# StEth32_Power.net
KiCad netlist of a schematic drawn in Altium Designer
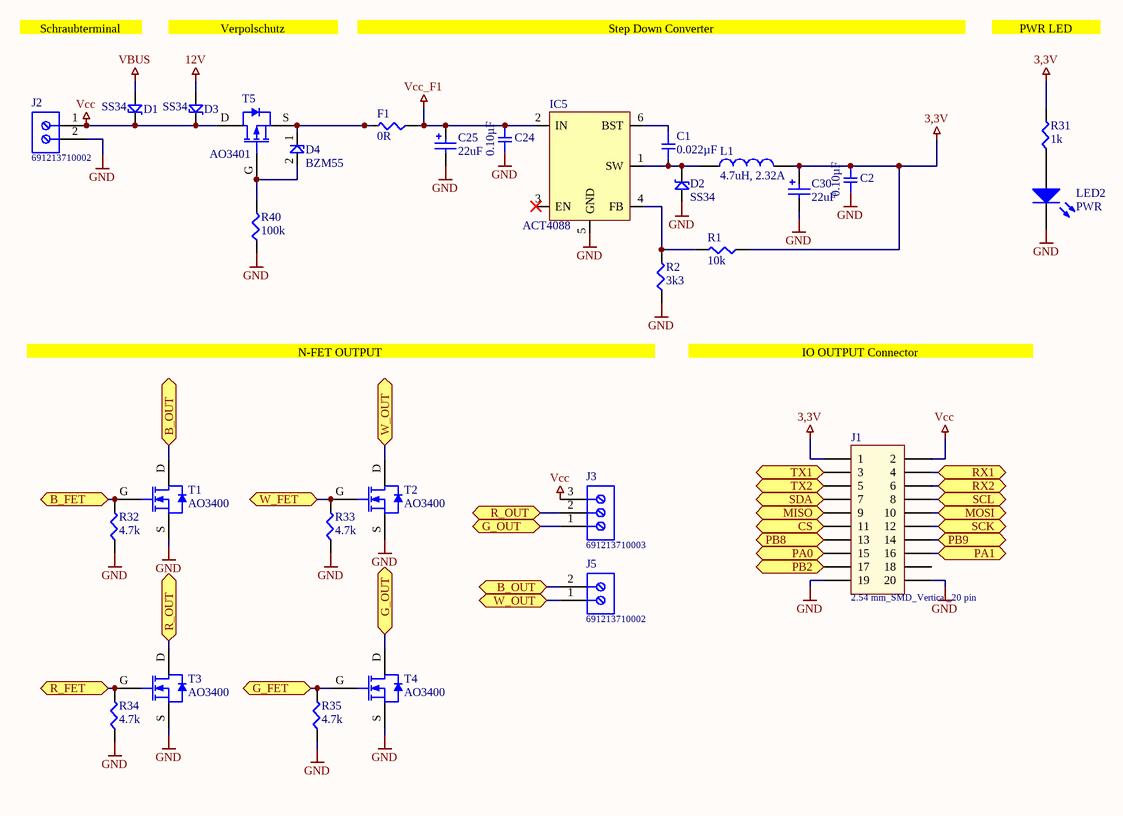
[diagram p0: StEth32_Power.SchDoc]

(export (version "E")
  (design (tool "Eeschema 10.0.6"))
  (components
    (comp (ref "C1")
      (value "0.022µF")
      (footprint "SMD-0603C")
      (description "CAP CER 0.022UF 50V X7R 0603")
      (fields
        (field (name "DIGI-KEY PART NUMBER") "490-5851-1-ND")
        (field (name "PART NUMBER") "GCJ188R71H223KA01D")
      )
      (libsource (lib "capacitor_murata_0603") (part "GCJ188R71H223KA01D"))
    )
    (comp (ref "C2")
      (value "0.10µF")
      (footprint "SMD-0603C")
      (description "CAP CER 0.1UF 16V X7R 0603")
      (fields
        (field (name "DIGI-KEY PART NUMBER") "490-8015-1-ND")
        (field (name "PART NUMBER") "GCM188R71C104KA37J")
      )
      (libsource (lib "capacitor_murata_0603") (part "GCM188R71C104KA37J"))
    )
    (comp (ref "C24")
      (value "0.10µF")
      (footprint "SMD-0603C")
      (description "CAP CER 0.1UF 16V X7R 0603")
      (fields
        (field (name "DIGI-KEY PART NUMBER") "490-8015-1-ND")
        (field (name "PART NUMBER") "GCM188R71C104KA37J")
      )
      (libsource (lib "capacitor_murata_0603") (part "GCM188R71C104KA37J"))
    )
    (comp (ref "C25")
      (value "22uF")
      (footprint "WCAP-ASLI_4x5.5")
      (description "WCAP-ASLI Aluminum Electrolytic Capacitors, size Ф4x5.5mm, 6.3V DC, 22uF")
      (fields (field (name "PART NUMBER") "865080140001") (field (name "PUBLISHER") "Wurth Elektronik"))
      (libsource (lib "ALTIUM-WCAP-ASLI-rev17a") (part "865080140001"))
    )
    (comp (ref "C30")
      (value "22uF")
      (footprint "WCAP-ASLI_4x5.5")
      (description "WCAP-ASLI Aluminum Electrolytic Capacitors, size Ф4x5.5mm, 6.3V DC, 22uF")
      (fields (field (name "PART NUMBER") "865080140001") (field (name "PUBLISHER") "Wurth Elektronik"))
      (libsource (lib "ALTIUM-WCAP-ASLI-rev17a") (part "865080140001"))
    )
    (comp (ref "D1")
      (value "SS34")
      (footprint "B240A")
      (description "Shottkydiode")
      (libsource (lib "MyLibs") (part "B240A"))
    )
    (comp (ref "D2")
      (value "SS34")
      (footprint "B240A")
      (description "Shottkydiode")
      (libsource (lib "MyLibs") (part "B240A"))
    )
    (comp (ref "D3")
      (value "SS34")
      (footprint "B240A")
      (description "Shottkydiode")
      (libsource (lib "MyLibs") (part "B240A"))
    )
    (comp (ref "D4") (value "BZM55") (footprint "SMD-0603-RES") (libsource (lib "MyLibs") (part "BZM55")))
    (comp (ref "F1")
      (value "0R")
      (footprint "SMD-0603-RES")
      (description "RES SMD 1K OHM 1% 1/10W 0603")
      (fields
        (field (name "PART NUMBER") "ERJ-3EKF1001V")
        (field (name "DIGI-KEY PART NUMBER") "P1.00KHCT-ND")
      )
      (libsource (lib "Panasonic_ERJ_0603") (part "ERJ-3EKF1001V"))
    )
    (comp (ref "IC5") (value "ACT4088") (footprint "SOT23-6") (libsource (lib "MyLibs") (part "ACT4088")))
    (comp (ref "J1")
      (value "2.54 mm_SMD_Vertical_20 pin")
      (footprint "61002021121")
      (description "Pin Header WR-PHD, pitch 2.54 mm, SMD, Vertical, dual row, 20 pin")
      (fields (field (name "PART NUMBER") "61002021121") (field (name "PUBLISHER") "Wurth Elektronik"))
      (libsource (lib "Altium_WR-PHD_PIN_HEADER_2_54 (rev18a)") (part "61002021121"))
    )
    (comp (ref "J2")
      (value "691213710002")
      (footprint "691213710002")
      (description "Serie 213 - 5.00 mm Horizontal Entry Modular with RisingCage Clamp WR-TBL, 2 pin")
      (fields (field (name "PUBLISHER") "Wurth Elektronik"))
      (libsource (lib "Altium_TBL_RISING_CAGE_SYSTEM (rev18b)") (part "691213710002"))
    )
    (comp (ref "J3")
      (value "691213710003")
      (footprint "691213710003")
      (description "Serie 213 - 5.00 mm Horizontal Entry Modular with RisingCage Clamp WR-TBL, 3 pin")
      (fields (field (name "PUBLISHER") "Wurth Elektronik"))
      (libsource (lib "Altium_TBL_RISING_CAGE_SYSTEM (rev18b)") (part "691213710003"))
    )
    (comp (ref "J5")
      (value "691213710002")
      (footprint "691213710002")
      (description "Serie 213 - 5.00 mm Horizontal Entry Modular with RisingCage Clamp WR-TBL, 2 pin")
      (fields (field (name "PUBLISHER") "Wurth Elektronik"))
      (libsource (lib "Altium_TBL_RISING_CAGE_SYSTEM (rev18b)") (part "691213710002"))
    )
    (comp (ref "L1")
      (value "4.7uH, 2.32A")
      (footprint "WE-PD_7332")
      (description "WE-PD SMT Power Inductor, size 7332, 4.7uH, 2.32A")
      (fields (field (name "PART NUMBER") "744778004") (field (name "PUBLISHER") "Wurth Elektronik"))
      (libsource (lib "ALTIUM-WE-PD-rev19b") (part "744778004"))
    )
    (comp (ref "LED2")
      (value "PWR")
      (footprint "0603_A")
      (description "SMD mono-color Chip LED, WL-SMCW, Super Red")
      (fields (field (name "PARTNUMBER") "150060SS75000"))
      (libsource (lib "WL-SMCW SMD chip LED top view mono-color waterclear") (part "150060SS75000"))
    )
    (comp (ref "R1")
      (value "10k")
      (footprint "SMD-0603-RES")
      (description "RES SMD 1K OHM 1% 1/10W 0603")
      (fields
        (field (name "PART NUMBER") "ERJ-3EKF1001V")
        (field (name "DIGI-KEY PART NUMBER") "P1.00KHCT-ND")
      )
      (libsource (lib "Panasonic_ERJ_0603") (part "ERJ-3EKF1001V"))
    )
    (comp (ref "R2")
      (value "3k3")
      (footprint "SMD-0603-RES")
      (description "RES SMD 1K OHM 1% 1/10W 0603")
      (fields
        (field (name "PART NUMBER") "ERJ-3EKF1001V")
        (field (name "DIGI-KEY PART NUMBER") "P1.00KHCT-ND")
      )
      (libsource (lib "Panasonic_ERJ_0603") (part "ERJ-3EKF1001V"))
    )
    (comp (ref "R31")
      (value "1k")
      (footprint "SMD-0603-RES")
      (description "RES SMD 1K OHM 1% 1/10W 0603")
      (fields
        (field (name "PART NUMBER") "ERJ-3EKF1001V")
        (field (name "DIGI-KEY PART NUMBER") "P1.00KHCT-ND")
      )
      (libsource (lib "Panasonic_ERJ_0603") (part "ERJ-3EKF1001V"))
    )
    (comp (ref "R32")
      (value "4.7k")
      (footprint "SMD-0603-RES")
      (description "RES SMD 4.7K OHM 1% 1/10W 0603")
      (fields
        (field (name "PART NUMBER") "ERJ-3EKF4701V")
        (field (name "DIGI-KEY PART NUMBER") "P4.70KHCT-ND")
      )
      (libsource (lib "Panasonic_ERJ_0603") (part "ERJ-3EKF4701V"))
    )
    (comp (ref "R33")
      (value "4.7k")
      (footprint "SMD-0603-RES")
      (description "RES SMD 4.7K OHM 1% 1/10W 0603")
      (fields
        (field (name "PART NUMBER") "ERJ-3EKF4701V")
        (field (name "DIGI-KEY PART NUMBER") "P4.70KHCT-ND")
      )
      (libsource (lib "Panasonic_ERJ_0603") (part "ERJ-3EKF4701V"))
    )
    (comp (ref "R34")
      (value "4.7k")
      (footprint "SMD-0603-RES")
      (description "RES SMD 4.7K OHM 1% 1/10W 0603")
      (fields
        (field (name "PART NUMBER") "ERJ-3EKF4701V")
        (field (name "DIGI-KEY PART NUMBER") "P4.70KHCT-ND")
      )
      (libsource (lib "Panasonic_ERJ_0603") (part "ERJ-3EKF4701V"))
    )
    (comp (ref "R35")
      (value "4.7k")
      (footprint "SMD-0603-RES")
      (description "RES SMD 4.7K OHM 1% 1/10W 0603")
      (fields
        (field (name "PART NUMBER") "ERJ-3EKF4701V")
        (field (name "DIGI-KEY PART NUMBER") "P4.70KHCT-ND")
      )
      (libsource (lib "Panasonic_ERJ_0603") (part "ERJ-3EKF4701V"))
    )
    (comp (ref "R40")
      (value "100k")
      (footprint "SMD-0603-RES")
      (description "RES SMD 4.7K OHM 1% 1/10W 0603")
      (fields
        (field (name "PART NUMBER") "ERJ-3EKF4701V")
        (field (name "DIGI-KEY PART NUMBER") "P4.70KHCT-ND")
      )
      (libsource (lib "Panasonic_ERJ_0603") (part "ERJ-3EKF4701V"))
    )
    (comp (ref "T1")
      (value "AO3400")
      (footprint "SOT23")
      (description "AO3400 MOSFET 30V")
      (libsource (lib "MyLibs") (part "AO3400"))
    )
    (comp (ref "T2")
      (value "AO3400")
      (footprint "SOT23")
      (description "AO3400 MOSFET 30V")
      (libsource (lib "MyLibs") (part "AO3400"))
    )
    (comp (ref "T3")
      (value "AO3400")
      (footprint "SOT23")
      (description "AO3400 MOSFET 30V")
      (libsource (lib "MyLibs") (part "AO3400"))
    )
    (comp (ref "T4")
      (value "AO3400")
      (footprint "SOT23")
      (description "AO3400 MOSFET 30V")
      (libsource (lib "MyLibs") (part "AO3400"))
    )
    (comp (ref "T5")
      (value "AO3401")
      (footprint "SOT23")
      (description "AO3401 MOSFET 30V")
      (libsource (lib "MyLibs") (part "AO3401"))
    )
  )
  (nets
    (net (code "1") (name "/B_FET") (class "Default")
      (node (ref "R32") (pin "2") (pinfunction "2_2") (pintype "passive"))
      (node (ref "T1") (pin "G") (pinfunction "G_G") (pintype "passive"))
    )
    (net (code "2") (name "/B_OUT") (class "Default")
      (node (ref "J5") (pin "2") (pinfunction "2_2") (pintype "passive"))
      (node (ref "T1") (pin "D") (pinfunction "D_D") (pintype "passive"))
    )
    (net (code "3") (name "/CS") (class "Default")
      (node (ref "J1") (pin "11") (pinfunction "11_11") (pintype "passive"))
    )
    (net (code "4") (name "/G_FET") (class "Default")
      (node (ref "R35") (pin "2") (pinfunction "2_2") (pintype "passive"))
      (node (ref "T4") (pin "G") (pinfunction "G_G") (pintype "passive"))
    )
    (net (code "5") (name "/G_OUT") (class "Default")
      (node (ref "J3") (pin "1") (pinfunction "1_1") (pintype "passive"))
      (node (ref "T4") (pin "D") (pinfunction "D_D") (pintype "passive"))
    )
    (net (code "6") (name "/MISO") (class "Default")
      (node (ref "J1") (pin "9") (pinfunction "9_9") (pintype "passive"))
    )
    (net (code "7") (name "/MOSI") (class "Default")
      (node (ref "J1") (pin "10") (pinfunction "10_10") (pintype "passive"))
    )
    (net (code "8") (name "/PA0") (class "Default")
      (node (ref "J1") (pin "15") (pinfunction "15_15") (pintype "passive"))
    )
    (net (code "9") (name "/PA1") (class "Default")
      (node (ref "J1") (pin "16") (pinfunction "16_16") (pintype "passive"))
    )
    (net (code "10") (name "/PB2") (class "Default")
      (node (ref "J1") (pin "17") (pinfunction "17_17") (pintype "passive"))
    )
    (net (code "11") (name "/PB8") (class "Default")
      (node (ref "J1") (pin "13") (pinfunction "13_13") (pintype "passive"))
    )
    (net (code "12") (name "/PB9") (class "Default")
      (node (ref "J1") (pin "14") (pinfunction "14_14") (pintype "passive"))
    )
    (net (code "13") (name "/RX1") (class "Default")
      (node (ref "J1") (pin "4") (pinfunction "4_4") (pintype "passive"))
    )
    (net (code "14") (name "/RX2") (class "Default")
      (node (ref "J1") (pin "6") (pinfunction "6_6") (pintype "passive"))
    )
    (net (code "15") (name "/R_FET") (class "Default")
      (node (ref "R34") (pin "2") (pinfunction "2_2") (pintype "passive"))
      (node (ref "T3") (pin "G") (pinfunction "G_G") (pintype "passive"))
    )
    (net (code "16") (name "/R_OUT") (class "Default")
      (node (ref "J3") (pin "2") (pinfunction "2_2") (pintype "passive"))
      (node (ref "T3") (pin "D") (pinfunction "D_D") (pintype "passive"))
    )
    (net (code "17") (name "/SCK") (class "Default")
      (node (ref "J1") (pin "12") (pinfunction "12_12") (pintype "passive"))
    )
    (net (code "18") (name "/SCL") (class "Default")
      (node (ref "J1") (pin "8") (pinfunction "8_8") (pintype "passive"))
    )
    (net (code "19") (name "/SDA") (class "Default")
      (node (ref "J1") (pin "7") (pinfunction "7_7") (pintype "passive"))
    )
    (net (code "20") (name "/TX1") (class "Default")
      (node (ref "J1") (pin "3") (pinfunction "3_3") (pintype "passive"))
    )
    (net (code "21") (name "/TX2") (class "Default")
      (node (ref "J1") (pin "5") (pinfunction "5_5") (pintype "passive"))
    )
    (net (code "22") (name "/W_FET") (class "Default")
      (node (ref "R33") (pin "2") (pinfunction "2_2") (pintype "passive"))
      (node (ref "T2") (pin "G") (pinfunction "G_G") (pintype "passive"))
    )
    (net (code "23") (name "/W_OUT") (class "Default")
      (node (ref "J5") (pin "1") (pinfunction "1_1") (pintype "passive"))
      (node (ref "T2") (pin "D") (pinfunction "D_D") (pintype "passive"))
    )
    (net (code "24") (name "3,3V") (class "Default")
      (node (ref "C2") (pin "1") (pinfunction "1_1") (pintype "passive"))
      (node (ref "C30") (pin "1") (pinfunction "P_1") (pintype "passive"))
      (node (ref "J1") (pin "1") (pinfunction "1_1") (pintype "passive"))
      (node (ref "L1") (pin "2") (pinfunction "2_2") (pintype "passive"))
      (node (ref "R1") (pin "1") (pinfunction "1_1") (pintype "passive"))
      (node (ref "R31") (pin "2") (pinfunction "2_2") (pintype "passive"))
    )
    (net (code "25") (name "12V") (class "Default")
      (node (ref "D3") (pin "A") (pinfunction "A_A") (pintype "passive"))
    )
    (net (code "26") (name "GND") (class "Default")
      (node (ref "C2") (pin "2") (pinfunction "2_2") (pintype "passive"))
      (node (ref "C24") (pin "2") (pinfunction "2_2") (pintype "passive"))
      (node (ref "C25") (pin "2") (pinfunction "N_2") (pintype "passive"))
      (node (ref "C30") (pin "2") (pinfunction "N_2") (pintype "passive"))
      (node (ref "D2") (pin "A") (pinfunction "A_A") (pintype "passive"))
      (node (ref "IC5") (pin "5") (pinfunction "GND_5") (pintype "passive"))
      (node (ref "J1") (pin "19") (pinfunction "19_19") (pintype "passive"))
      (node (ref "J1") (pin "20") (pinfunction "20_20") (pintype "passive"))
      (node (ref "J2") (pin "2") (pinfunction "2_2") (pintype "passive"))
      (node (ref "LED2") (pin "1") (pinfunction "K_1") (pintype "passive"))
      (node (ref "R2") (pin "1") (pinfunction "1_1") (pintype "passive"))
      (node (ref "R32") (pin "1") (pinfunction "1_1") (pintype "passive"))
      (node (ref "R33") (pin "1") (pinfunction "1_1") (pintype "passive"))
      (node (ref "R34") (pin "1") (pinfunction "1_1") (pintype "passive"))
      (node (ref "R35") (pin "1") (pinfunction "1_1") (pintype "passive"))
      (node (ref "R40") (pin "1") (pinfunction "1_1") (pintype "passive"))
      (node (ref "T1") (pin "S") (pinfunction "S_S") (pintype "passive"))
      (node (ref "T2") (pin "S") (pinfunction "S_S") (pintype "passive"))
      (node (ref "T3") (pin "S") (pinfunction "S_S") (pintype "passive"))
      (node (ref "T4") (pin "S") (pinfunction "S_S") (pintype "passive"))
    )
    (net (code "27") (name "Net-(D4-1-Pad2)") (class "Default")
      (node (ref "D4") (pin "2") (pinfunction "1_2") (pintype "passive"))
      (node (ref "R40") (pin "2") (pinfunction "2_2") (pintype "passive"))
      (node (ref "T5") (pin "G") (pinfunction "G_G") (pintype "passive"))
    )
    (net (code "28") (name "Net-(D4-Pad1)") (class "Default")
      (node (ref "D4") (pin "1") (pinfunction "1_1") (pintype "passive"))
      (node (ref "F1") (pin "2") (pinfunction "2_2") (pintype "passive"))
      (node (ref "T5") (pin "S") (pinfunction "S_S") (pintype "passive"))
    )
    (net (code "29") (name "Net-(IC5-BST)") (class "Default")
      (node (ref "C1") (pin "1") (pinfunction "1_1") (pintype "passive"))
      (node (ref "IC5") (pin "6") (pinfunction "BST_6") (pintype "passive"))
    )
    (net (code "30") (name "Net-(IC5-FB)") (class "Default")
      (node (ref "IC5") (pin "4") (pinfunction "FB_4") (pintype "passive"))
      (node (ref "R1") (pin "2") (pinfunction "2_2") (pintype "passive"))
      (node (ref "R2") (pin "2") (pinfunction "2_2") (pintype "passive"))
    )
    (net (code "31") (name "Net-(IC5-SW)") (class "Default")
      (node (ref "C1") (pin "2") (pinfunction "2_2") (pintype "passive"))
      (node (ref "D2") (pin "K") (pinfunction "K_K") (pintype "passive"))
      (node (ref "IC5") (pin "1") (pinfunction "SW_1") (pintype "passive"))
      (node (ref "L1") (pin "1") (pinfunction "1_1") (pintype "passive"))
    )
    (net (code "32") (name "Net-(LED2-A)") (class "Default")
      (node (ref "LED2") (pin "2") (pinfunction "A_2") (pintype "passive"))
      (node (ref "R31") (pin "1") (pinfunction "1_1") (pintype "passive"))
    )
    (net (code "33") (name "VBUS") (class "Default")
      (node (ref "D1") (pin "A") (pinfunction "A_A") (pintype "passive"))
    )
    (net (code "34") (name "Vcc") (class "Default")
      (node (ref "D1") (pin "K") (pinfunction "K_K") (pintype "passive"))
      (node (ref "D3") (pin "K") (pinfunction "K_K") (pintype "passive"))
      (node (ref "J1") (pin "2") (pinfunction "2_2") (pintype "passive"))
      (node (ref "J2") (pin "1") (pinfunction "1_1") (pintype "passive"))
      (node (ref "J3") (pin "3") (pinfunction "3_3") (pintype "passive"))
      (node (ref "T5") (pin "D") (pinfunction "D_D") (pintype "passive"))
    )
    (net (code "35") (name "Vcc_F1") (class "Default")
      (node (ref "C24") (pin "1") (pinfunction "1_1") (pintype "passive"))
      (node (ref "C25") (pin "1") (pinfunction "P_1") (pintype "passive"))
      (node (ref "F1") (pin "1") (pinfunction "1_1") (pintype "passive"))
      (node (ref "IC5") (pin "2") (pinfunction "IN_2") (pintype "passive"))
    )
    (net (code "36") (name "unconnected-(IC5-EN-Pad3)") (class "Default")
      (node (ref "IC5") (pin "3") (pinfunction "EN_3") (pintype "passive+no_connect"))
    )
    (net (code "37") (name "unconnected-(J1-Pad18)") (class "Default")
      (node (ref "J1") (pin "18") (pinfunction "18_18") (pintype "passive"))
    )
  )
)
